# MSP430.net
KiCad netlist of a schematic drawn in Altium Designer
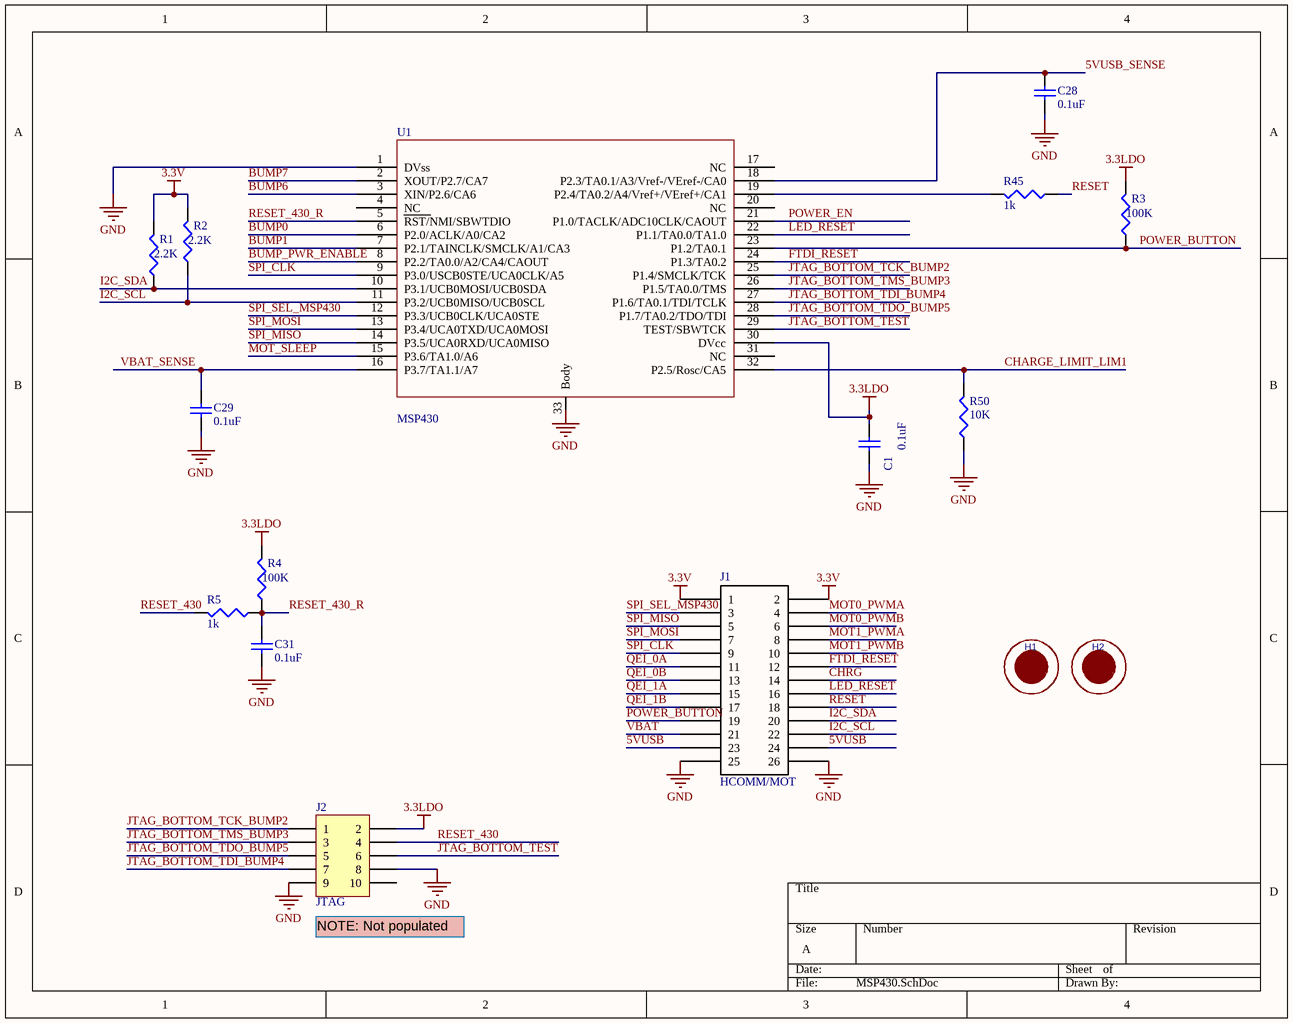
[diagram p0: MSP430.SchDoc]

(export (version "E")
  (design (tool "Eeschema 10.0.6"))
  (components
    (comp (ref "C1")
      (value "0.1uF")
      (footprint "CAPC1005L")
      (description "Capacitor (Semiconductor SIM Model)")
      (fields
        (field (name "PART NUMBER") "GRM155R71C104KA88D")
        (field (name "MANUFACTURER") "Murata")
        (field (name "PUBLISHER") "Altium Limited")
      )
      (libsource (lib "Miscellaneous Devices") (part "Cap Semi"))
    )
    (comp (ref "C28")
      (value "0.1uF")
      (footprint "CAPC1005L")
      (description "Capacitor (Semiconductor SIM Model)")
      (fields
        (field (name "PART NUMBER") "GRM155R71C104KA88D")
        (field (name "MANUFACTURER") "Murata")
        (field (name "PUBLISHER") "Altium Limited")
      )
      (libsource (lib "Miscellaneous Devices") (part "Cap Semi"))
    )
    (comp (ref "C29")
      (value "0.1uF")
      (footprint "CAPC1005L")
      (description "Capacitor (Semiconductor SIM Model)")
      (fields
        (field (name "PART NUMBER") "GRM155R71C104KA88D")
        (field (name "MANUFACTURER") "Murata")
        (field (name "PUBLISHER") "Altium Limited")
      )
      (libsource (lib "Miscellaneous Devices") (part "Cap Semi"))
    )
    (comp (ref "C31")
      (value "0.1uF")
      (footprint "CAPC1005L")
      (description "Capacitor (Semiconductor SIM Model)")
      (fields
        (field (name "PART NUMBER") "GRM155R71C104KA88D")
        (field (name "MANUFACTURER") "Murata")
        (field (name "PUBLISHER") "Altium Limited")
      )
      (libsource (lib "Miscellaneous Devices") (part "Cap Semi"))
    )
    (comp (ref "H1")
      (value "H_FID_F40")
      (footprint "F40")
      (libsource (lib "UnifiedLibraryDBlib") (part "H_FID_F40"))
    )
    (comp (ref "H2")
      (value "H_FID_F40")
      (footprint "F40")
      (libsource (lib "UnifiedLibraryDBlib") (part "H_FID_F40"))
    )
    (comp (ref "J1")
      (value "HCOMM/MOT")
      (footprint "HeaderSM 13x2")
      (description "Header, 2X20, 50mil, IDC")
      (fields (field (name "PART NUMBER") "SHF-113-01-l-E-SM-LC") (field (name "MANUFACTURER") "Samtec"))
      (libsource (lib "mrone") (part "HCOMM/HMOT"))
    )
    (comp (ref "J2")
      (value "JTAG")
      (footprint "HDR2X5")
      (description "Header, 5-Pin, Dual row")
      (fields (field (name "PUBLISHER") "Altium Limited"))
      (libsource (lib "Miscellaneous Connectors") (part "Header 5X2"))
    )
    (comp (ref "R1")
      (value "2.2K")
      (footprint "RESC1608L")
      (description "Resistor")
      (fields
        (field (name "PART NUMBER") "ERJ-3GEYJ-222V")
        (field (name "MANUFACTURER") "Panasonic")
        (field (name "PUBLISHER") "Altium Limited")
      )
      (libsource (lib "Miscellaneous Devices") (part "Res3"))
    )
    (comp (ref "R2")
      (value "2.2K")
      (footprint "RESC1608L")
      (description "Resistor")
      (fields
        (field (name "PART NUMBER") "ERJ-3GEYJ-222V")
        (field (name "MANUFACTURER") "Panasonic")
        (field (name "PUBLISHER") "Altium Limited")
      )
      (libsource (lib "Miscellaneous Devices") (part "Res3"))
    )
    (comp (ref "R3")
      (value "100K")
      (footprint "RESC1608L")
      (description "Resistor")
      (fields
        (field (name "PART NUMBER") "ERJ-3GEYJ104V")
        (field (name "MANUFACTURER") "Panasonic")
        (field (name "PUBLISHER") "Altium Limited")
      )
      (libsource (lib "Miscellaneous Devices") (part "Res3"))
    )
    (comp (ref "R4")
      (value "100K")
      (footprint "RESC1608L")
      (description "Resistor")
      (fields
        (field (name "PART NUMBER") "ERJ-3GEYJ104V")
        (field (name "MANUFACTURER") "Panasonic")
        (field (name "PUBLISHER") "Altium Limited")
      )
      (libsource (lib "Miscellaneous Devices") (part "Res3"))
    )
    (comp (ref "R5")
      (value "1k")
      (footprint "RESC1608L")
      (description "Resistor")
      (fields
        (field (name "PART NUMBER") "ERJ-3GEYJ102V")
        (field (name "MANUFACTURER") "Panasonic")
        (field (name "PUBLISHER") "Altium Limited")
      )
      (libsource (lib "Miscellaneous Devices") (part "Res3"))
    )
    (comp (ref "R45")
      (value "1k")
      (footprint "RESC1608L")
      (description "Resistor")
      (fields
        (field (name "PART NUMBER") "ERJ-3GEYJ102V")
        (field (name "MANUFACTURER") "Panasonic")
        (field (name "PUBLISHER") "Altium Limited")
      )
      (libsource (lib "Miscellaneous Devices") (part "Res3"))
    )
    (comp (ref "R50")
      (value "10K")
      (footprint "RESC1608L")
      (description "Resistor")
      (fields
        (field (name "PART NUMBER") "71-CRCW0603-10K-E3")
        (field (name "MANUFACTURER") "Vishay Dale")
        (field (name "PUBLISHER") "Altium Limited")
      )
      (libsource (lib "Miscellaneous Devices") (part "Res3"))
    )
    (comp (ref "U1")
      (value "MSP430")
      (footprint "MSP430_32PIN")
      (fields (field (name "PART NUMBER") "MSP430F2132IRHBR") (field (name "MANUFACTURER") "TI"))
      (libsource (lib "mrone") (part "MSP430_32pin"))
    )
  )
  (nets
    (net (code "1") (name "/5VUSB") (class "Default")
      (node (ref "J1") (pin "23") (pinfunction "23_23") (pintype "passive"))
      (node (ref "J1") (pin "24") (pinfunction "24_24") (pintype "passive"))
    )
    (net (code "2") (name "/5VUSB_SENSE") (class "Default")
      (node (ref "C28") (pin "2") (pinfunction "2_2") (pintype "passive"))
      (node (ref "U1") (pin "18") (pinfunction "P2.3/TA0.1/A3/Vref-/VEref-/CA0_18") (pintype "passive"))
    )
    (net (code "3") (name "/BUMP0") (class "Default")
      (node (ref "U1") (pin "6") (pinfunction "P2.0/ACLK/A0/CA2_6") (pintype "passive"))
    )
    (net (code "4") (name "/BUMP1") (class "Default")
      (node (ref "U1") (pin "7") (pinfunction "P2.1/TAINCLK/SMCLK/A1/CA3_7") (pintype "passive"))
    )
    (net (code "5") (name "/BUMP6") (class "Default")
      (node (ref "U1") (pin "3") (pinfunction "XIN/P2.6/CA6_3") (pintype "passive"))
    )
    (net (code "6") (name "/BUMP7") (class "Default")
      (node (ref "U1") (pin "2") (pinfunction "XOUT/P2.7/CA7_2") (pintype "passive"))
    )
    (net (code "7") (name "/BUMP_PWR_ENABLE") (class "Default")
      (node (ref "U1") (pin "8") (pinfunction "P2.2/TA0.0/A2/CA4/CAOUT_8") (pintype "passive"))
    )
    (net (code "8") (name "/CHARGE_LIMIT_LIM1") (class "Default")
      (node (ref "R50") (pin "2") (pinfunction "2_2") (pintype "passive"))
      (node (ref "U1") (pin "32") (pinfunction "P2.5/Rosc/CA5_32") (pintype "passive"))
    )
    (net (code "9") (name "/CHRG") (class "Default")
      (node (ref "J1") (pin "14") (pinfunction "14_14") (pintype "passive"))
    )
    (net (code "10") (name "/FTDI_RESET") (class "Default")
      (node (ref "J1") (pin "12") (pinfunction "12_12") (pintype "passive"))
      (node (ref "U1") (pin "24") (pinfunction "P1.3/TA0.2_24") (pintype "passive"))
    )
    (net (code "11") (name "/I2C_SCL") (class "Default")
      (node (ref "J1") (pin "22") (pinfunction "22_22") (pintype "passive"))
      (node (ref "R2") (pin "1") (pinfunction "1_1") (pintype "passive"))
      (node (ref "U1") (pin "11") (pinfunction "P3.2/UCB0MISO/UCB0SCL_11") (pintype "passive"))
    )
    (net (code "12") (name "/I2C_SDA") (class "Default")
      (node (ref "J1") (pin "20") (pinfunction "20_20") (pintype "passive"))
      (node (ref "R1") (pin "1") (pinfunction "1_1") (pintype "passive"))
      (node (ref "U1") (pin "10") (pinfunction "P3.1/UCB0MOSI/UCB0SDA_10") (pintype "passive"))
    )
    (net (code "13") (name "/JTAG_BOTTOM_TCK_BUMP2") (class "Default")
      (node (ref "J2") (pin "1") (pinfunction "1_1") (pintype "passive"))
      (node (ref "U1") (pin "25") (pinfunction "P1.4/SMCLK/TCK_25") (pintype "passive"))
    )
    (net (code "14") (name "/JTAG_BOTTOM_TDI_BUMP4") (class "Default")
      (node (ref "J2") (pin "7") (pinfunction "7_7") (pintype "passive"))
      (node (ref "U1") (pin "27") (pinfunction "P1.6/TA0.1/TDI/TCLK_27") (pintype "passive"))
    )
    (net (code "15") (name "/JTAG_BOTTOM_TDO_BUMP5") (class "Default")
      (node (ref "J2") (pin "5") (pinfunction "5_5") (pintype "passive"))
      (node (ref "U1") (pin "28") (pinfunction "P1.7/TA0.2/TDO/TDI_28") (pintype "passive"))
    )
    (net (code "16") (name "/JTAG_BOTTOM_TEST") (class "Default")
      (node (ref "J2") (pin "6") (pinfunction "6_6") (pintype "passive"))
      (node (ref "U1") (pin "29") (pinfunction "TEST/SBWTCK_29") (pintype "passive"))
    )
    (net (code "17") (name "/JTAG_BOTTOM_TMS_BUMP3") (class "Default")
      (node (ref "J2") (pin "3") (pinfunction "3_3") (pintype "passive"))
      (node (ref "U1") (pin "26") (pinfunction "P1.5/TA0.0/TMS_26") (pintype "passive"))
    )
    (net (code "18") (name "/LED_RESET") (class "Default")
      (node (ref "J1") (pin "16") (pinfunction "16_16") (pintype "passive"))
      (node (ref "U1") (pin "22") (pinfunction "P1.1/TA0.0/TA1.0_22") (pintype "passive"))
    )
    (net (code "19") (name "/MOT0_PWMA") (class "Default")
      (node (ref "J1") (pin "4") (pinfunction "4_4") (pintype "passive"))
    )
    (net (code "20") (name "/MOT0_PWMB") (class "Default")
      (node (ref "J1") (pin "6") (pinfunction "6_6") (pintype "passive"))
    )
    (net (code "21") (name "/MOT1_PWMA") (class "Default")
      (node (ref "J1") (pin "8") (pinfunction "8_8") (pintype "passive"))
    )
    (net (code "22") (name "/MOT1_PWMB") (class "Default")
      (node (ref "J1") (pin "10") (pinfunction "10_10") (pintype "passive"))
    )
    (net (code "23") (name "/MOT_SLEEP") (class "Default")
      (node (ref "U1") (pin "15") (pinfunction "P3.6/TA1.0/A6_15") (pintype "passive"))
    )
    (net (code "24") (name "/POWER_BUTTON") (class "Default")
      (node (ref "J1") (pin "19") (pinfunction "19_19") (pintype "passive"))
      (node (ref "R3") (pin "1") (pinfunction "1_1") (pintype "passive"))
      (node (ref "U1") (pin "23") (pinfunction "P1.2/TA0.1_23") (pintype "passive"))
    )
    (net (code "25") (name "/POWER_EN") (class "Default")
      (node (ref "U1") (pin "21") (pinfunction "P1.0/TACLK/ADC10CLK/CAOUT_21") (pintype "passive"))
    )
    (net (code "26") (name "/QEI_0A") (class "Default")
      (node (ref "J1") (pin "11") (pinfunction "11_11") (pintype "passive"))
    )
    (net (code "27") (name "/QEI_0B") (class "Default")
      (node (ref "J1") (pin "13") (pinfunction "13_13") (pintype "passive"))
    )
    (net (code "28") (name "/QEI_1A") (class "Default")
      (node (ref "J1") (pin "15") (pinfunction "15_15") (pintype "passive"))
    )
    (net (code "29") (name "/QEI_1B") (class "Default")
      (node (ref "J1") (pin "17") (pinfunction "17_17") (pintype "passive"))
    )
    (net (code "30") (name "/RESET") (class "Default")
      (node (ref "J1") (pin "18") (pinfunction "18_18") (pintype "passive"))
      (node (ref "R45") (pin "1") (pinfunction "1_1") (pintype "passive"))
    )
    (net (code "31") (name "/RESET_430") (class "Default")
      (node (ref "J2") (pin "4") (pinfunction "4_4") (pintype "passive"))
      (node (ref "R5") (pin "2") (pinfunction "2_2") (pintype "passive"))
    )
    (net (code "32") (name "/RESET_430_R") (class "Default")
      (node (ref "C31") (pin "2") (pinfunction "2_2") (pintype "passive"))
      (node (ref "R4") (pin "1") (pinfunction "1_1") (pintype "passive"))
      (node (ref "R5") (pin "1") (pinfunction "1_1") (pintype "passive"))
      (node (ref "U1") (pin "5") (pinfunction "RST/NMI/SBWTDIO_5") (pintype "passive"))
    )
    (net (code "33") (name "/SPI_CLK") (class "Default")
      (node (ref "J1") (pin "9") (pinfunction "9_9") (pintype "passive"))
      (node (ref "U1") (pin "9") (pinfunction "P3.0/USCB0STE/UCA0CLK/A5_9") (pintype "passive"))
    )
    (net (code "34") (name "/SPI_MISO") (class "Default")
      (node (ref "J1") (pin "5") (pinfunction "5_5") (pintype "passive"))
      (node (ref "U1") (pin "14") (pinfunction "P3.5/UCA0RXD/UCA0MISO_14") (pintype "passive"))
    )
    (net (code "35") (name "/SPI_MOSI") (class "Default")
      (node (ref "J1") (pin "7") (pinfunction "7_7") (pintype "passive"))
      (node (ref "U1") (pin "13") (pinfunction "P3.4/UCA0TXD/UCA0MOSI_13") (pintype "passive"))
    )
    (net (code "36") (name "/SPI_SEL_MSP430") (class "Default")
      (node (ref "J1") (pin "3") (pinfunction "3_3") (pintype "passive"))
      (node (ref "U1") (pin "12") (pinfunction "P3.3/UCB0CLK/UCA0STE_12") (pintype "passive"))
    )
    (net (code "37") (name "/VBAT") (class "Default")
      (node (ref "J1") (pin "21") (pinfunction "21_21") (pintype "passive"))
    )
    (net (code "38") (name "/VBAT_SENSE") (class "Default")
      (node (ref "C29") (pin "2") (pinfunction "2_2") (pintype "passive"))
      (node (ref "U1") (pin "16") (pinfunction "P3.7/TA1.1/A7_16") (pintype "passive"))
    )
    (net (code "39") (name "3.3LDO") (class "Default")
      (node (ref "C1") (pin "2") (pinfunction "2_2") (pintype "passive"))
      (node (ref "J2") (pin "2") (pinfunction "2_2") (pintype "passive"))
      (node (ref "R3") (pin "2") (pinfunction "2_2") (pintype "passive"))
      (node (ref "R4") (pin "2") (pinfunction "2_2") (pintype "passive"))
      (node (ref "U1") (pin "30") (pinfunction "DVcc_30") (pintype "passive"))
    )
    (net (code "40") (name "3.3V") (class "Default")
      (node (ref "J1") (pin "1") (pinfunction "1_1") (pintype "passive"))
      (node (ref "J1") (pin "2") (pinfunction "2_2") (pintype "passive"))
      (node (ref "R1") (pin "2") (pinfunction "2_2") (pintype "passive"))
      (node (ref "R2") (pin "2") (pinfunction "2_2") (pintype "passive"))
    )
    (net (code "41") (name "GND") (class "Default")
      (node (ref "C1") (pin "1") (pinfunction "1_1") (pintype "passive"))
      (node (ref "C28") (pin "1") (pinfunction "1_1") (pintype "passive"))
      (node (ref "C29") (pin "1") (pinfunction "1_1") (pintype "passive"))
      (node (ref "C31") (pin "1") (pinfunction "1_1") (pintype "passive"))
      (node (ref "J1") (pin "25") (pinfunction "25_25") (pintype "passive"))
      (node (ref "J1") (pin "26") (pinfunction "26_26") (pintype "passive"))
      (node (ref "J2") (pin "8") (pinfunction "8_8") (pintype "passive"))
      (node (ref "J2") (pin "9") (pinfunction "9_9") (pintype "passive"))
      (node (ref "R50") (pin "1") (pinfunction "1_1") (pintype "passive"))
      (node (ref "U1") (pin "1") (pinfunction "DVss_1") (pintype "passive"))
      (node (ref "U1") (pin "33") (pinfunction "Body_33") (pintype "power_in"))
    )
    (net (code "42") (name "Net-(U1-P2.4{slash}TA0.2{slash}A4{slash}Vref+{slash}VEref+{slash}CA1)") (class "Default")
      (node (ref "R45") (pin "2") (pinfunction "2_2") (pintype "passive"))
      (node (ref "U1") (pin "19") (pinfunction "P2.4/TA0.2/A4/Vref+/VEref+/CA1_19") (pintype "passive"))
    )
    (net (code "43") (name "unconnected-(H1-Pad1)") (class "Default")
      (node (ref "H1") (pin "1") (pinfunction "1_1") (pintype "passive"))
    )
    (net (code "44") (name "unconnected-(H2-Pad1)") (class "Default")
      (node (ref "H2") (pin "1") (pinfunction "1_1") (pintype "passive"))
    )
    (net (code "45") (name "unconnected-(J2-Pad10)") (class "Default")
      (node (ref "J2") (pin "10") (pinfunction "10_10") (pintype "passive"))
    )
    (net (code "46") (name "unconnected-(U1-NC-Pad4)") (class "Default")
      (node (ref "U1") (pin "4") (pinfunction "NC_4") (pintype "passive"))
    )
    (net (code "47") (name "unconnected-(U1-NC-Pad17)") (class "Default")
      (node (ref "U1") (pin "17") (pinfunction "NC_17") (pintype "passive"))
    )
    (net (code "48") (name "unconnected-(U1-NC-Pad20)") (class "Default")
      (node (ref "U1") (pin "20") (pinfunction "NC_20") (pintype "passive"))
    )
    (net (code "49") (name "unconnected-(U1-NC-Pad31)") (class "Default")
      (node (ref "U1") (pin "31") (pinfunction "NC_31") (pintype "passive"))
    )
  )
)
